# p2gs-001.net
KiCad netlist of a schematic drawn in EAGLE
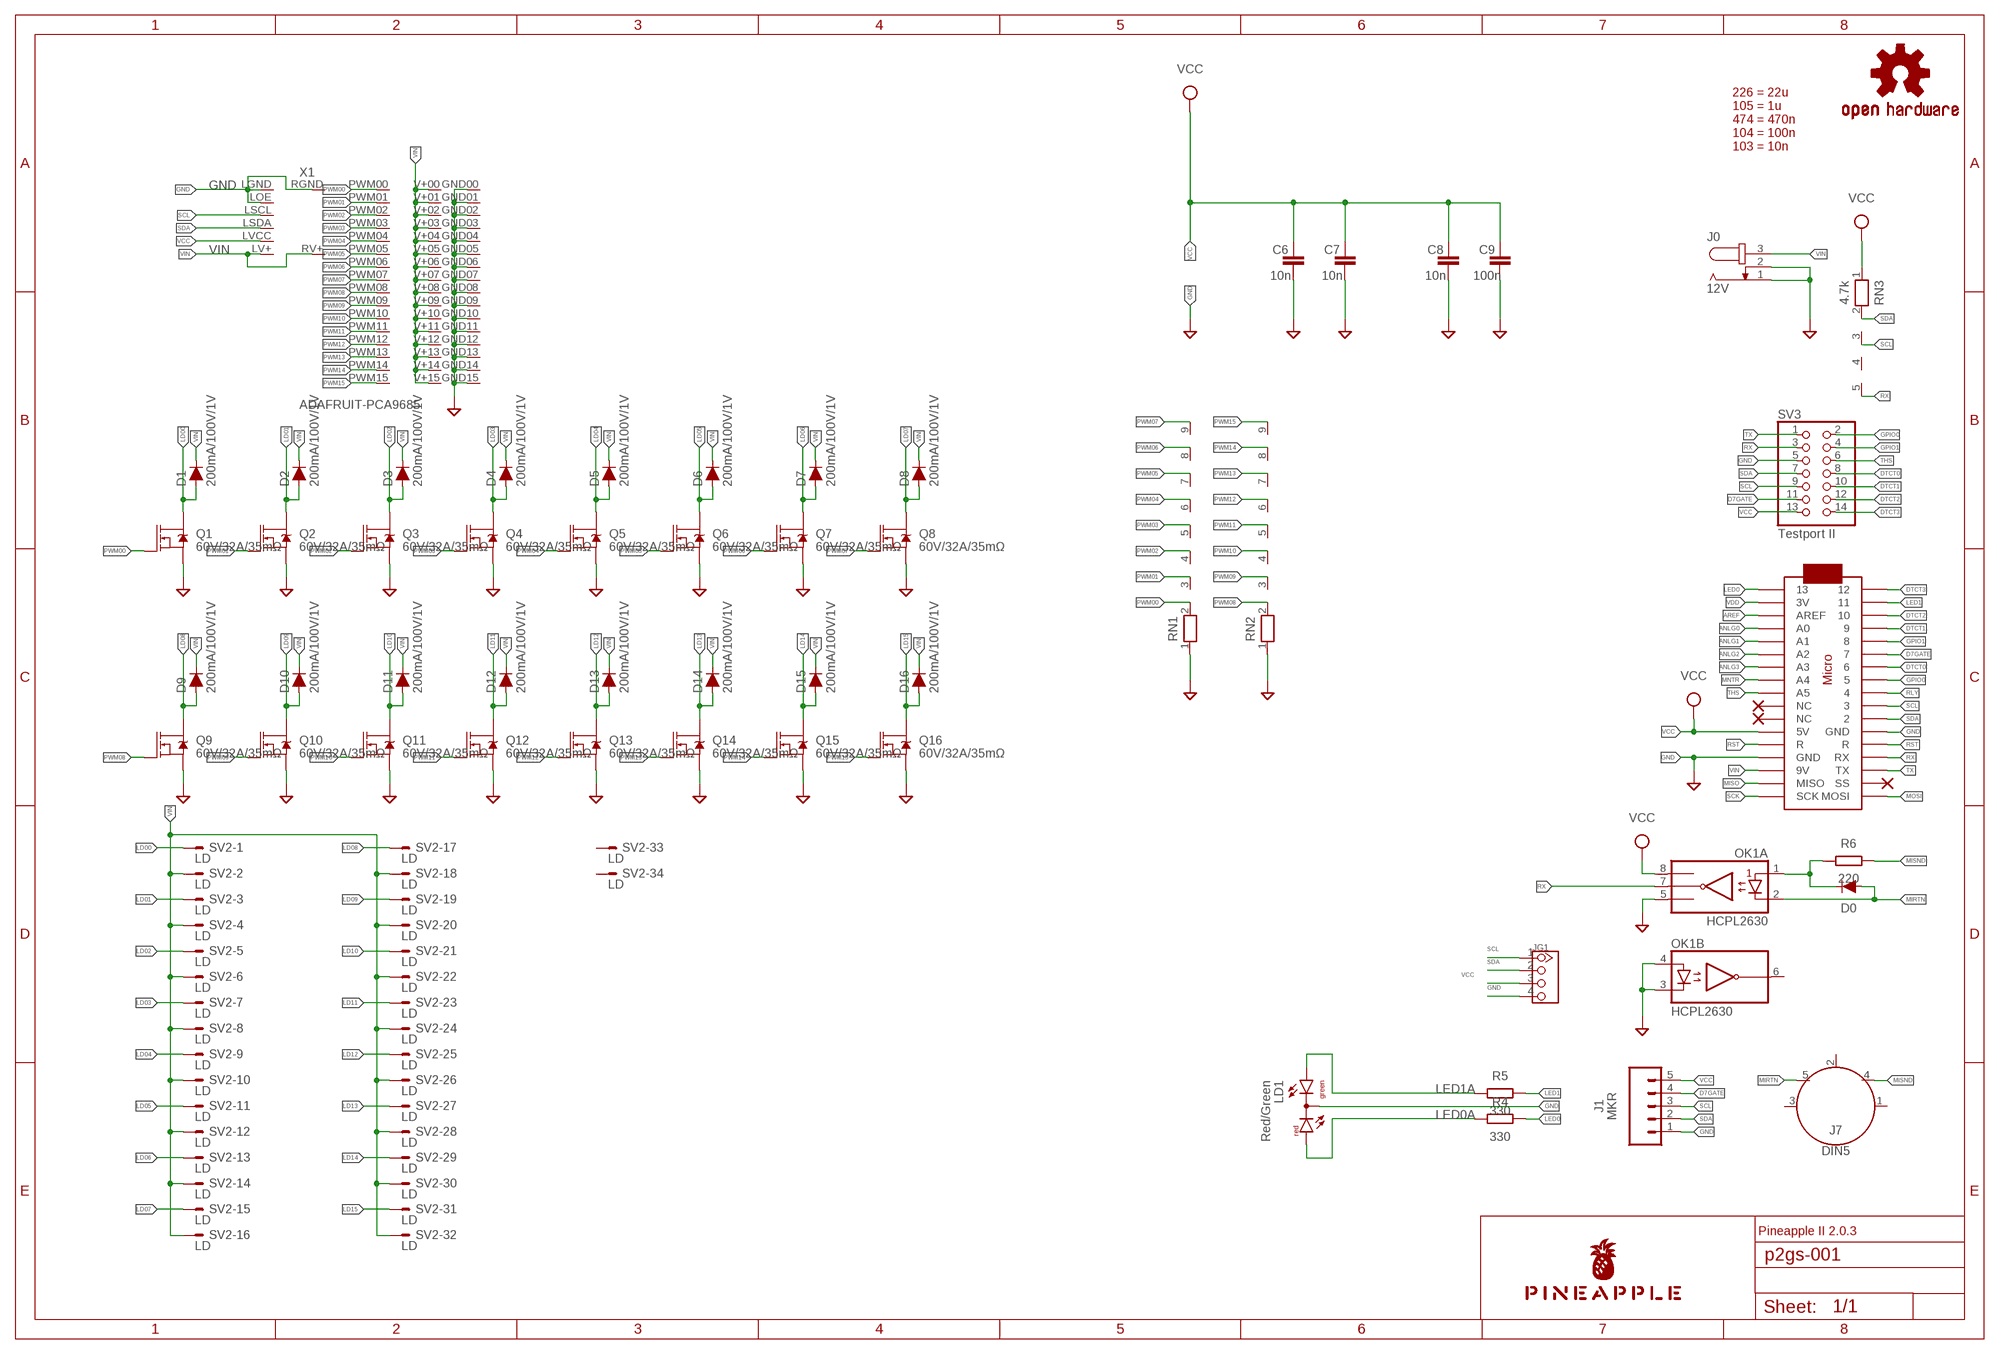
[diagram p0: schematic, sheet 1]

(export (version "E")
  (design (tool "Eeschema 10.0.6"))
  (components
    (comp (ref "C6")
      (value "10n")
      (footprint "eagle-import:C025-024X044")
      (libsource (lib "eagle-import") (part "C-EU025-024X044"))
    )
    (comp (ref "C7")
      (value "10n")
      (footprint "eagle-import:C025-024X044")
      (libsource (lib "eagle-import") (part "C-EU025-024X044"))
    )
    (comp (ref "C8")
      (value "10n")
      (footprint "eagle-import:C025-024X044")
      (libsource (lib "eagle-import") (part "C-EU025-024X044"))
    )
    (comp (ref "C9")
      (value "100n")
      (footprint "eagle-import:C025-024X044")
      (libsource (lib "eagle-import") (part "C-EU025-024X044"))
    )
    (comp (ref "D0")
      (value "DIODE-1N4148")
      (footprint "eagle-import:DIODE-1N4148")
      (libsource (lib "eagle-import") (part "DIODE-1N4148"))
    )
    (comp (ref "D1")
      (value "200mA/100V/1V")
      (footprint "eagle-import:DIODE-1N4148")
      (libsource (lib "eagle-import") (part "DIODE-1N4148"))
    )
    (comp (ref "D2")
      (value "200mA/100V/1V")
      (footprint "eagle-import:DIODE-1N4148")
      (libsource (lib "eagle-import") (part "DIODE-1N4148"))
    )
    (comp (ref "D3")
      (value "200mA/100V/1V")
      (footprint "eagle-import:DIODE-1N4148")
      (libsource (lib "eagle-import") (part "DIODE-1N4148"))
    )
    (comp (ref "D4")
      (value "200mA/100V/1V")
      (footprint "eagle-import:DIODE-1N4148")
      (libsource (lib "eagle-import") (part "DIODE-1N4148"))
    )
    (comp (ref "D5")
      (value "200mA/100V/1V")
      (footprint "eagle-import:DIODE-1N4148")
      (libsource (lib "eagle-import") (part "DIODE-1N4148"))
    )
    (comp (ref "D6")
      (value "200mA/100V/1V")
      (footprint "eagle-import:DIODE-1N4148")
      (libsource (lib "eagle-import") (part "DIODE-1N4148"))
    )
    (comp (ref "D7")
      (value "200mA/100V/1V")
      (footprint "eagle-import:DIODE-1N4148")
      (libsource (lib "eagle-import") (part "DIODE-1N4148"))
    )
    (comp (ref "D8")
      (value "200mA/100V/1V")
      (footprint "eagle-import:DIODE-1N4148")
      (libsource (lib "eagle-import") (part "DIODE-1N4148"))
    )
    (comp (ref "D9")
      (value "200mA/100V/1V")
      (footprint "eagle-import:DIODE-1N4148")
      (libsource (lib "eagle-import") (part "DIODE-1N4148"))
    )
    (comp (ref "D10")
      (value "200mA/100V/1V")
      (footprint "eagle-import:DIODE-1N4148")
      (libsource (lib "eagle-import") (part "DIODE-1N4148"))
    )
    (comp (ref "D11")
      (value "200mA/100V/1V")
      (footprint "eagle-import:DIODE-1N4148")
      (libsource (lib "eagle-import") (part "DIODE-1N4148"))
    )
    (comp (ref "D12")
      (value "200mA/100V/1V")
      (footprint "eagle-import:DIODE-1N4148")
      (libsource (lib "eagle-import") (part "DIODE-1N4148"))
    )
    (comp (ref "D13")
      (value "200mA/100V/1V")
      (footprint "eagle-import:DIODE-1N4148")
      (libsource (lib "eagle-import") (part "DIODE-1N4148"))
    )
    (comp (ref "D14")
      (value "200mA/100V/1V")
      (footprint "eagle-import:DIODE-1N4148")
      (libsource (lib "eagle-import") (part "DIODE-1N4148"))
    )
    (comp (ref "D15")
      (value "200mA/100V/1V")
      (footprint "eagle-import:DIODE-1N4148")
      (libsource (lib "eagle-import") (part "DIODE-1N4148"))
    )
    (comp (ref "D16")
      (value "200mA/100V/1V")
      (footprint "eagle-import:DIODE-1N4148")
      (libsource (lib "eagle-import") (part "DIODE-1N4148"))
    )
    (comp (ref "J0")
      (value "12V")
      (footprint "eagle-import:SPC4077")
      (libsource (lib "eagle-import") (part "JACK-PLUG0"))
    )
    (comp (ref "J1")
      (value "MKR")
      (footprint "eagle-import:JST-5-PTH")
      (libsource (lib "eagle-import") (part "CONN_05JST"))
    )
    (comp (ref "J7")
      (value "DIN5")
      (footprint "eagle-import:DIN5-RA-PTH")
      (libsource (lib "eagle-import") (part "DIN5"))
    )
    (comp (ref "JG1")
      (value "TWIG-4P-2.0'90D'")
      (footprint "eagle-import:4P-2.0-90D")
      (libsource (lib "eagle-import") (part "TWIG-4P-2.0'90D'"))
    )
    (comp (ref "LD1")
      (value "Red/Green")
      (footprint "eagle-import:DUOLED-C-5MM")
      (libsource (lib "eagle-import") (part "DUOLED-RG-C"))
    )
    (comp (ref "LOGO1")
      (value "OSHW-LOGOS-COPPER")
      (footprint "eagle-import:OSHW-LOGO-S_COPPER")
      (libsource (lib "eagle-import") (part "OSHW-LOGOS-COPPER"))
    )
    (comp (ref "MC1")
      (value "ARDUINOMICRO")
      (footprint "eagle-import:ARDUINOMICRO")
      (libsource (lib "eagle-import") (part "ARDUINOMICRO"))
    )
    (comp (ref "OK1")
      (value "HCPL2630")
      (footprint "eagle-import:DIL08")
      (fields (field (name "MF") "AGILENT TECHNOLOGIES") (field (name "MPN") "HCPL-2630-000E"))
      (libsource (lib "eagle-import") (part "HCPL2630"))
    )
    (comp (ref "Q1")
      (value "60V/32A/35mΩ")
      (footprint "eagle-import:TO220V")
      (libsource (lib "eagle-import") (part "MOSFET-NCH-FQP30N06L"))
    )
    (comp (ref "Q2")
      (value "60V/32A/35mΩ")
      (footprint "eagle-import:TO220V")
      (libsource (lib "eagle-import") (part "MOSFET-NCH-FQP30N06L"))
    )
    (comp (ref "Q3")
      (value "60V/32A/35mΩ")
      (footprint "eagle-import:TO220V")
      (libsource (lib "eagle-import") (part "MOSFET-NCH-FQP30N06L"))
    )
    (comp (ref "Q4")
      (value "60V/32A/35mΩ")
      (footprint "eagle-import:TO220V")
      (libsource (lib "eagle-import") (part "MOSFET-NCH-FQP30N06L"))
    )
    (comp (ref "Q5")
      (value "60V/32A/35mΩ")
      (footprint "eagle-import:TO220V")
      (libsource (lib "eagle-import") (part "MOSFET-NCH-FQP30N06L"))
    )
    (comp (ref "Q6")
      (value "60V/32A/35mΩ")
      (footprint "eagle-import:TO220V")
      (libsource (lib "eagle-import") (part "MOSFET-NCH-FQP30N06L"))
    )
    (comp (ref "Q7")
      (value "60V/32A/35mΩ")
      (footprint "eagle-import:TO220V")
      (libsource (lib "eagle-import") (part "MOSFET-NCH-FQP30N06L"))
    )
    (comp (ref "Q8")
      (value "60V/32A/35mΩ")
      (footprint "eagle-import:TO220V")
      (libsource (lib "eagle-import") (part "MOSFET-NCH-FQP30N06L"))
    )
    (comp (ref "Q9")
      (value "60V/32A/35mΩ")
      (footprint "eagle-import:TO220V")
      (libsource (lib "eagle-import") (part "MOSFET-NCH-FQP30N06L"))
    )
    (comp (ref "Q10")
      (value "60V/32A/35mΩ")
      (footprint "eagle-import:TO220V")
      (libsource (lib "eagle-import") (part "MOSFET-NCH-FQP30N06L"))
    )
    (comp (ref "Q11")
      (value "60V/32A/35mΩ")
      (footprint "eagle-import:TO220V")
      (libsource (lib "eagle-import") (part "MOSFET-NCH-FQP30N06L"))
    )
    (comp (ref "Q12")
      (value "60V/32A/35mΩ")
      (footprint "eagle-import:TO220V")
      (libsource (lib "eagle-import") (part "MOSFET-NCH-FQP30N06L"))
    )
    (comp (ref "Q13")
      (value "60V/32A/35mΩ")
      (footprint "eagle-import:TO220V")
      (libsource (lib "eagle-import") (part "MOSFET-NCH-FQP30N06L"))
    )
    (comp (ref "Q14")
      (value "60V/32A/35mΩ")
      (footprint "eagle-import:TO220V")
      (libsource (lib "eagle-import") (part "MOSFET-NCH-FQP30N06L"))
    )
    (comp (ref "Q15")
      (value "60V/32A/35mΩ")
      (footprint "eagle-import:TO220V")
      (libsource (lib "eagle-import") (part "MOSFET-NCH-FQP30N06L"))
    )
    (comp (ref "Q16")
      (value "60V/32A/35mΩ")
      (footprint "eagle-import:TO220V")
      (libsource (lib "eagle-import") (part "MOSFET-NCH-FQP30N06L"))
    )
    (comp (ref "R4")
      (value "330")
      (footprint "eagle-import:0204_5")
      (libsource (lib "eagle-import") (part "R-EU_0204/5"))
    )
    (comp (ref "R5")
      (value "330")
      (footprint "eagle-import:0204_5")
      (libsource (lib "eagle-import") (part "R-EU_0204/5"))
    )
    (comp (ref "R6")
      (value "220")
      (footprint "eagle-import:0204_5")
      (libsource (lib "eagle-import") (part "R-EU_0204/5"))
    )
    (comp (ref "RN1")
      (value "RN08")
      (footprint "eagle-import:RN-9")
      (libsource (lib "eagle-import") (part "RN08"))
    )
    (comp (ref "RN2")
      (value "RN08")
      (footprint "eagle-import:RN-9")
      (libsource (lib "eagle-import") (part "RN08"))
    )
    (comp (ref "RN3")
      (value "4.7k")
      (footprint "eagle-import:RN-5")
      (libsource (lib "eagle-import") (part "RN04"))
    )
    (comp (ref "SV2")
      (value "LD")
      (footprint "eagle-import:ML34L")
      (libsource (lib "eagle-import") (part "ML34LE"))
    )
    (comp (ref "SV3")
      (value "Testport II")
      (footprint "eagle-import:2X07")
      (libsource (lib "eagle-import") (part "PINHD-2X7"))
    )
    (comp (ref "U$1")
      (value "PINEAPPLE450_SILK")
      (footprint "eagle-import:PINEAPPLE450_SILK")
      (libsource (lib "eagle-import") (part "PINEAPPLE450_SILK"))
    )
    (comp (ref "X1")
      (value "ADAFRUIT-PCA9685")
      (footprint "eagle-import:ADAFRUIT-PCA9685-FOOTPRINT")
      (libsource (lib "eagle-import") (part "ADAFRUIT-PCA9685"))
    )
  )
  (nets
    (net (code "1") (name "/LED0A") (class "Default")
      (node (ref "LD1") (pin "AR") (pinfunction "AR_AR") (pintype "passive"))
      (node (ref "R4") (pin "1") (pinfunction "1_1") (pintype "passive"))
    )
    (net (code "2") (name "/LED1A") (class "Default")
      (node (ref "LD1") (pin "AX") (pinfunction "AG_AX") (pintype "passive"))
      (node (ref "R5") (pin "1") (pinfunction "1_1") (pintype "passive"))
    )
    (net (code "3") (name "ANLG0") (class "Default")
      (node (ref "MC1") (pin "P$31") (pinfunction "A0_P$31") (pintype "bidirectional"))
    )
    (net (code "4") (name "ANLG1") (class "Default")
      (node (ref "MC1") (pin "P$30") (pinfunction "A1_P$30") (pintype "bidirectional"))
    )
    (net (code "5") (name "ANLG2") (class "Default")
      (node (ref "MC1") (pin "P$29") (pinfunction "A2_P$29") (pintype "bidirectional"))
    )
    (net (code "6") (name "ANLG3") (class "Default")
      (node (ref "MC1") (pin "P$28") (pinfunction "A3_P$28") (pintype "bidirectional"))
    )
    (net (code "7") (name "AREF") (class "Default")
      (node (ref "MC1") (pin "P$32") (pinfunction "AREF_P$32") (pintype "bidirectional"))
    )
    (net (code "8") (name "D7GATE") (class "Default")
      (node (ref "J1") (pin "4") (pinfunction "4_4") (pintype "passive"))
      (node (ref "MC1") (pin "P$6") (pinfunction "7_P$6") (pintype "bidirectional"))
      (node (ref "SV3") (pin "11") (pinfunction "11_11") (pintype "passive"))
    )
    (net (code "9") (name "DTCT0") (class "Default")
      (node (ref "MC1") (pin "P$7") (pinfunction "6_P$7") (pintype "bidirectional"))
      (node (ref "SV3") (pin "8") (pinfunction "8_8") (pintype "passive"))
    )
    (net (code "10") (name "DTCT1") (class "Default")
      (node (ref "MC1") (pin "P$4") (pinfunction "9_P$4") (pintype "bidirectional"))
      (node (ref "SV3") (pin "10") (pinfunction "10_10") (pintype "passive"))
    )
    (net (code "11") (name "DTCT2") (class "Default")
      (node (ref "MC1") (pin "P$3") (pinfunction "10_P$3") (pintype "bidirectional"))
      (node (ref "SV3") (pin "12") (pinfunction "12_12") (pintype "passive"))
    )
    (net (code "12") (name "DTCT3") (class "Default")
      (node (ref "MC1") (pin "P$1") (pinfunction "12_P$1") (pintype "bidirectional"))
      (node (ref "SV3") (pin "14") (pinfunction "14_14") (pintype "passive"))
    )
    (net (code "13") (name "GND") (class "Default")
      (node (ref "C6") (pin "2") (pinfunction "2_2") (pintype "passive"))
      (node (ref "C7") (pin "2") (pinfunction "2_2") (pintype "passive"))
      (node (ref "C8") (pin "2") (pinfunction "2_2") (pintype "passive"))
      (node (ref "C9") (pin "2") (pinfunction "2_2") (pintype "passive"))
      (node (ref "J0") (pin "1") (pinfunction "1_1") (pintype "passive"))
      (node (ref "J0") (pin "2") (pinfunction "2_2") (pintype "passive"))
      (node (ref "J1") (pin "1") (pinfunction "1_1") (pintype "passive"))
      (node (ref "JG1") (pin "4") (pinfunction "4_4") (pintype "bidirectional"))
      (node (ref "LD1") (pin "C") (pinfunction "C_C") (pintype "passive"))
      (node (ref "MC1") (pin "P$12") (pinfunction "GND_P$12") (pintype "bidirectional"))
      (node (ref "MC1") (pin "P$21") (pinfunction "GND_P$21") (pintype "bidirectional"))
      (node (ref "OK1") (pin "3") (pinfunction "C2_3") (pintype "passive"))
      (node (ref "OK1") (pin "4") (pinfunction "A2_4") (pintype "passive"))
      (node (ref "OK1") (pin "5") (pinfunction "GND_5") (pintype "passive"))
      (node (ref "Q1") (pin "3") (pinfunction "S_3") (pintype "bidirectional"))
      (node (ref "Q10") (pin "3") (pinfunction "S_3") (pintype "bidirectional"))
      (node (ref "Q11") (pin "3") (pinfunction "S_3") (pintype "bidirectional"))
      (node (ref "Q12") (pin "3") (pinfunction "S_3") (pintype "bidirectional"))
      (node (ref "Q13") (pin "3") (pinfunction "S_3") (pintype "bidirectional"))
      (node (ref "Q14") (pin "3") (pinfunction "S_3") (pintype "bidirectional"))
      (node (ref "Q15") (pin "3") (pinfunction "S_3") (pintype "bidirectional"))
      (node (ref "Q16") (pin "3") (pinfunction "S_3") (pintype "bidirectional"))
      (node (ref "Q2") (pin "3") (pinfunction "S_3") (pintype "bidirectional"))
      (node (ref "Q3") (pin "3") (pinfunction "S_3") (pintype "bidirectional"))
      (node (ref "Q4") (pin "3") (pinfunction "S_3") (pintype "bidirectional"))
      (node (ref "Q5") (pin "3") (pinfunction "S_3") (pintype "bidirectional"))
      (node (ref "Q6") (pin "3") (pinfunction "S_3") (pintype "bidirectional"))
      (node (ref "Q7") (pin "3") (pinfunction "S_3") (pintype "bidirectional"))
      (node (ref "Q8") (pin "3") (pinfunction "S_3") (pintype "bidirectional"))
      (node (ref "Q9") (pin "3") (pinfunction "S_3") (pintype "bidirectional"))
      (node (ref "RN1") (pin "1") (pinfunction "1_1") (pintype "passive"))
      (node (ref "RN2") (pin "1") (pinfunction "1_1") (pintype "passive"))
      (node (ref "SV3") (pin "5") (pinfunction "5_5") (pintype "passive"))
      (node (ref "X1") (pin "GND00") (pinfunction "45_GND00") (pintype "passive"))
      (node (ref "X1") (pin "GND01") (pinfunction "46_GND01") (pintype "passive"))
      (node (ref "X1") (pin "GND02") (pinfunction "47_GND02") (pintype "passive"))
      (node (ref "X1") (pin "GND03") (pinfunction "48_GND03") (pintype "passive"))
      (node (ref "X1") (pin "GND04") (pinfunction "49_GND04") (pintype "passive"))
      (node (ref "X1") (pin "GND05") (pinfunction "50_GND05") (pintype "passive"))
      (node (ref "X1") (pin "GND06") (pinfunction "51_GND06") (pintype "passive"))
      (node (ref "X1") (pin "GND07") (pinfunction "52_GND07") (pintype "passive"))
      (node (ref "X1") (pin "GND08") (pinfunction "53_GND08") (pintype "passive"))
      (node (ref "X1") (pin "GND09") (pinfunction "54_GND09") (pintype "passive"))
      (node (ref "X1") (pin "GND10") (pinfunction "55_GND10") (pintype "passive"))
      (node (ref "X1") (pin "GND11") (pinfunction "56_GND11") (pintype "passive"))
      (node (ref "X1") (pin "GND12") (pinfunction "57_GND12") (pintype "passive"))
      (node (ref "X1") (pin "GND13") (pinfunction "58_GND13") (pintype "passive"))
      (node (ref "X1") (pin "GND14") (pinfunction "59_GND14") (pintype "passive"))
      (node (ref "X1") (pin "GND15") (pinfunction "60_GND15") (pintype "passive"))
      (node (ref "X1") (pin "LGND") (pinfunction "1_LGND") (pintype "passive"))
      (node (ref "X1") (pin "LOE") (pinfunction "2_LOE") (pintype "passive"))
      (node (ref "X1") (pin "RGND") (pinfunction "7_RGND") (pintype "passive"))
    )
    (net (code "14") (name "GPIO0") (class "Default")
      (node (ref "MC1") (pin "P$8") (pinfunction "5_P$8") (pintype "bidirectional"))
      (node (ref "SV3") (pin "2") (pinfunction "2_2") (pintype "passive"))
    )
    (net (code "15") (name "GPIO1") (class "Default")
      (node (ref "MC1") (pin "P$5") (pinfunction "8_P$5") (pintype "bidirectional"))
      (node (ref "SV3") (pin "4") (pinfunction "4_4") (pintype "passive"))
    )
    (net (code "16") (name "LD00") (class "Default")
      (node (ref "D1") (pin "A") (pinfunction "A_A") (pintype "passive"))
      (node (ref "Q1") (pin "2") (pinfunction "D_2") (pintype "bidirectional"))
      (node (ref "SV2") (pin "1") (pinfunction "S_1") (pintype "passive"))
    )
    (net (code "17") (name "LD01") (class "Default")
      (node (ref "D2") (pin "A") (pinfunction "A_A") (pintype "passive"))
      (node (ref "Q2") (pin "2") (pinfunction "D_2") (pintype "bidirectional"))
      (node (ref "SV2") (pin "3") (pinfunction "S_3") (pintype "passive"))
    )
    (net (code "18") (name "LD02") (class "Default")
      (node (ref "D3") (pin "A") (pinfunction "A_A") (pintype "passive"))
      (node (ref "Q3") (pin "2") (pinfunction "D_2") (pintype "bidirectional"))
      (node (ref "SV2") (pin "5") (pinfunction "S_5") (pintype "passive"))
    )
    (net (code "19") (name "LD03") (class "Default")
      (node (ref "D4") (pin "A") (pinfunction "A_A") (pintype "passive"))
      (node (ref "Q4") (pin "2") (pinfunction "D_2") (pintype "bidirectional"))
      (node (ref "SV2") (pin "7") (pinfunction "S_7") (pintype "passive"))
    )
    (net (code "20") (name "LD04") (class "Default")
      (node (ref "D5") (pin "A") (pinfunction "A_A") (pintype "passive"))
      (node (ref "Q5") (pin "2") (pinfunction "D_2") (pintype "bidirectional"))
      (node (ref "SV2") (pin "9") (pinfunction "S_9") (pintype "passive"))
    )
    (net (code "21") (name "LD05") (class "Default")
      (node (ref "D6") (pin "A") (pinfunction "A_A") (pintype "passive"))
      (node (ref "Q6") (pin "2") (pinfunction "D_2") (pintype "bidirectional"))
      (node (ref "SV2") (pin "11") (pinfunction "S_11") (pintype "passive"))
    )
    (net (code "22") (name "LD06") (class "Default")
      (node (ref "D7") (pin "A") (pinfunction "A_A") (pintype "passive"))
      (node (ref "Q7") (pin "2") (pinfunction "D_2") (pintype "bidirectional"))
      (node (ref "SV2") (pin "13") (pinfunction "S_13") (pintype "passive"))
    )
    (net (code "23") (name "LD07") (class "Default")
      (node (ref "D8") (pin "A") (pinfunction "A_A") (pintype "passive"))
      (node (ref "Q8") (pin "2") (pinfunction "D_2") (pintype "bidirectional"))
      (node (ref "SV2") (pin "15") (pinfunction "S_15") (pintype "passive"))
    )
    (net (code "24") (name "LD08") (class "Default")
      (node (ref "D9") (pin "A") (pinfunction "A_A") (pintype "passive"))
      (node (ref "Q9") (pin "2") (pinfunction "D_2") (pintype "bidirectional"))
      (node (ref "SV2") (pin "17") (pinfunction "S_17") (pintype "passive"))
    )
    (net (code "25") (name "LD09") (class "Default")
      (node (ref "D10") (pin "A") (pinfunction "A_A") (pintype "passive"))
      (node (ref "Q10") (pin "2") (pinfunction "D_2") (pintype "bidirectional"))
      (node (ref "SV2") (pin "19") (pinfunction "S_19") (pintype "passive"))
    )
    (net (code "26") (name "LD10") (class "Default")
      (node (ref "D11") (pin "A") (pinfunction "A_A") (pintype "passive"))
      (node (ref "Q11") (pin "2") (pinfunction "D_2") (pintype "bidirectional"))
      (node (ref "SV2") (pin "21") (pinfunction "S_21") (pintype "passive"))
    )
    (net (code "27") (name "LD11") (class "Default")
      (node (ref "D12") (pin "A") (pinfunction "A_A") (pintype "passive"))
      (node (ref "Q12") (pin "2") (pinfunction "D_2") (pintype "bidirectional"))
      (node (ref "SV2") (pin "23") (pinfunction "S_23") (pintype "passive"))
    )
    (net (code "28") (name "LD12") (class "Default")
      (node (ref "D13") (pin "A") (pinfunction "A_A") (pintype "passive"))
      (node (ref "Q13") (pin "2") (pinfunction "D_2") (pintype "bidirectional"))
      (node (ref "SV2") (pin "25") (pinfunction "S_25") (pintype "passive"))
    )
    (net (code "29") (name "LD13") (class "Default")
      (node (ref "D14") (pin "A") (pinfunction "A_A") (pintype "passive"))
      (node (ref "Q14") (pin "2") (pinfunction "D_2") (pintype "bidirectional"))
      (node (ref "SV2") (pin "27") (pinfunction "S_27") (pintype "passive"))
    )
    (net (code "30") (name "LD14") (class "Default")
      (node (ref "D15") (pin "A") (pinfunction "A_A") (pintype "passive"))
      (node (ref "Q15") (pin "2") (pinfunction "D_2") (pintype "bidirectional"))
      (node (ref "SV2") (pin "29") (pinfunction "S_29") (pintype "passive"))
    )
    (net (code "31") (name "LD15") (class "Default")
      (node (ref "D16") (pin "A") (pinfunction "A_A") (pintype "passive"))
      (node (ref "Q16") (pin "2") (pinfunction "D_2") (pintype "bidirectional"))
      (node (ref "SV2") (pin "31") (pinfunction "S_31") (pintype "passive"))
    )
    (net (code "32") (name "LED0") (class "Default")
      (node (ref "MC1") (pin "P$34") (pinfunction "13_P$34") (pintype "bidirectional"))
      (node (ref "R4") (pin "2") (pinfunction "2_2") (pintype "passive"))
    )
    (net (code "33") (name "LED1") (class "Default")
      (node (ref "MC1") (pin "P$2") (pinfunction "11_P$2") (pintype "bidirectional"))
      (node (ref "R5") (pin "2") (pinfunction "2_2") (pintype "passive"))
    )
    (net (code "34") (name "MIRTN") (class "Default")
      (node (ref "D0") (pin "A") (pinfunction "A_A") (pintype "passive"))
      (node (ref "J7") (pin "5") (pinfunction "5_5") (pintype "bidirectional"))
      (node (ref "OK1") (pin "2") (pinfunction "C1_2") (pintype "passive"))
    )
    (net (code "35") (name "MISND") (class "Default")
      (node (ref "J7") (pin "4") (pinfunction "4_4") (pintype "bidirectional"))
      (node (ref "R6") (pin "2") (pinfunction "2_2") (pintype "passive"))
    )
    (net (code "36") (name "MISO") (class "Default")
      (node (ref "MC1") (pin "P$19") (pinfunction "MISO_P$19") (pintype "bidirectional"))
    )
    (net (code "37") (name "MNTR") (class "Default")
      (node (ref "MC1") (pin "P$27") (pinfunction "A4_P$27") (pintype "bidirectional"))
    )
    (net (code "38") (name "MOSI") (class "Default")
      (node (ref "MC1") (pin "P$17") (pinfunction "MOSI_P$17") (pintype "bidirectional"))
    )
    (net (code "39") (name "Net-(OK1A-A1)") (class "Default")
      (node (ref "D0") (pin "C") (pinfunction "C_C") (pintype "passive"))
      (node (ref "OK1") (pin "1") (pinfunction "A1_1") (pintype "passive"))
      (node (ref "R6") (pin "1") (pinfunction "1_1") (pintype "passive"))
    )
    (net (code "40") (name "PWM00") (class "Default")
      (node (ref "Q1") (pin "1") (pinfunction "G_1") (pintype "bidirectional"))
      (node (ref "RN1") (pin "2") (pinfunction "2_2") (pintype "passive"))
      (node (ref "X1") (pin "PWM00") (pinfunction "13_PWM00") (pintype "passive"))
    )
    (net (code "41") (name "PWM01") (class "Default")
      (node (ref "Q2") (pin "1") (pinfunction "G_1") (pintype "bidirectional"))
      (node (ref "RN1") (pin "3") (pinfunction "3_3") (pintype "passive"))
      (node (ref "X1") (pin "PWM01") (pinfunction "14_PWM01") (pintype "passive"))
    )
    (net (code "42") (name "PWM02") (class "Default")
      (node (ref "Q3") (pin "1") (pinfunction "G_1") (pintype "bidirectional"))
      (node (ref "RN1") (pin "4") (pinfunction "4_4") (pintype "passive"))
      (node (ref "X1") (pin "PWM02") (pinfunction "15_PWM02") (pintype "passive"))
    )
    (net (code "43") (name "PWM03") (class "Default")
      (node (ref "Q4") (pin "1") (pinfunction "G_1") (pintype "bidirectional"))
      (node (ref "RN1") (pin "5") (pinfunction "5_5") (pintype "passive"))
      (node (ref "X1") (pin "PWM03") (pinfunction "16_PWM03") (pintype "passive"))
    )
    (net (code "44") (name "PWM04") (class "Default")
      (node (ref "Q5") (pin "1") (pinfunction "G_1") (pintype "bidirectional"))
      (node (ref "RN1") (pin "6") (pinfunction "6_6") (pintype "passive"))
      (node (ref "X1") (pin "PWM04") (pinfunction "17_PWM04") (pintype "passive"))
    )
    (net (code "45") (name "PWM05") (class "Default")
      (node (ref "Q6") (pin "1") (pinfunction "G_1") (pintype "bidirectional"))
      (node (ref "RN1") (pin "7") (pinfunction "7_7") (pintype "passive"))
      (node (ref "X1") (pin "PWM05") (pinfunction "18_PWM05") (pintype "passive"))
    )
    (net (code "46") (name "PWM06") (class "Default")
      (node (ref "Q7") (pin "1") (pinfunction "G_1") (pintype "bidirectional"))
      (node (ref "RN1") (pin "8") (pinfunction "8_8") (pintype "passive"))
      (node (ref "X1") (pin "PWM06") (pinfunction "19_PWM06") (pintype "passive"))
    )
    (net (code "47") (name "PWM07") (class "Default")
      (node (ref "Q8") (pin "1") (pinfunction "G_1") (pintype "bidirectional"))
      (node (ref "RN1") (pin "9") (pinfunction "9_9") (pintype "passive"))
      (node (ref "X1") (pin "PWM07") (pinfunction "20_PWM07") (pintype "passive"))
    )
    (net (code "48") (name "PWM08") (class "Default")
      (node (ref "Q9") (pin "1") (pinfunction "G_1") (pintype "bidirectional"))
      (node (ref "RN2") (pin "2") (pinfunction "2_2") (pintype "passive"))
      (node (ref "X1") (pin "PWM08") (pinfunction "21_PWM08") (pintype "passive"))
    )
    (net (code "49") (name "PWM09") (class "Default")
      (node (ref "Q10") (pin "1") (pinfunction "G_1") (pintype "bidirectional"))
      (node (ref "RN2") (pin "3") (pinfunction "3_3") (pintype "passive"))
      (node (ref "X1") (pin "PWM09") (pinfunction "22_PWM09") (pintype "passive"))
    )
    (net (code "50") (name "PWM10") (class "Default")
      (node (ref "Q11") (pin "1") (pinfunction "G_1") (pintype "bidirectional"))
      (node (ref "RN2") (pin "4") (pinfunction "4_4") (pintype "passive"))
      (node (ref "X1") (pin "PWM10") (pinfunction "23_PWM10") (pintype "passive"))
    )
    (net (code "51") (name "PWM11") (class "Default")
      (node (ref "Q12") (pin "1") (pinfunction "G_1") (pintype "bidirectional"))
      (node (ref "RN2") (pin "5") (pinfunction "5_5") (pintype "passive"))
      (node (ref "X1") (pin "PWM11") (pinfunction "24_PWM11") (pintype "passive"))
    )
    (net (code "52") (name "PWM12") (class "Default")
      (node (ref "Q13") (pin "1") (pinfunction "G_1") (pintype "bidirectional"))
      (node (ref "RN2") (pin "6") (pinfunction "6_6") (pintype "passive"))
      (node (ref "X1") (pin "PWM12") (pinfunction "25_PWM12") (pintype "passive"))
    )
    (net (code "53") (name "PWM13") (class "Default")
      (node (ref "Q14") (pin "1") (pinfunction "G_1") (pintype "bidirectional"))
      (node (ref "RN2") (pin "7") (pinfunction "7_7") (pintype "passive"))
      (node (ref "X1") (pin "PWM13") (pinfunction "26_PWM13") (pintype "passive"))
    )
    (net (code "54") (name "PWM14") (class "Default")
      (node (ref "Q15") (pin "1") (pinfunction "G_1") (pintype "bidirectional"))
      (node (ref "RN2") (pin "8") (pinfunction "8_8") (pintype "passive"))
      (node (ref "X1") (pin "PWM14") (pinfunction "27_PWM14") (pintype "passive"))
    )
    (net (code "55") (name "PWM15") (class "Default")
      (node (ref "Q16") (pin "1") (pinfunction "G_1") (pintype "bidirectional"))
      (node (ref "RN2") (pin "9") (pinfunction "9_9") (pintype "passive"))
      (node (ref "X1") (pin "PWM15") (pinfunction "28_PWM15") (pintype "passive"))
    )
    (net (code "56") (name "RLY") (class "Default")
      (node (ref "MC1") (pin "P$9") (pinfunction "4_P$9") (pintype "bidirectional"))
    )
    (net (code "57") (name "RST") (class "Default")
      (node (ref "MC1") (pin "P$13") (pinfunction "R_P$13") (pintype "bidirectional"))
      (node (ref "MC1") (pin "P$22") (pinfunction "R_P$22") (pintype "bidirectional"))
    )
    (net (code "58") (name "RX") (class "Default")
      (node (ref "MC1") (pin "P$14") (pinfunction "RX_P$14") (pintype "bidirectional"))
      (node (ref "OK1") (pin "7") (pinfunction "VO1_7") (pintype "passive"))
      (node (ref "RN3") (pin "5") (pinfunction "5_5") (pintype "passive"))
      (node (ref "SV3") (pin "3") (pinfunction "3_3") (pintype "passive"))
    )
    (net (code "59") (name "SCK") (class "Default")
      (node (ref "MC1") (pin "P$18") (pinfunction "SCK_P$18") (pintype "bidirectional"))
    )
    (net (code "60") (name "SCL") (class "Default")
      (node (ref "J1") (pin "3") (pinfunction "3_3") (pintype "passive"))
      (node (ref "JG1") (pin "1") (pinfunction "1_1") (pintype "bidirectional"))
      (node (ref "MC1") (pin "P$10") (pinfunction "3_P$10") (pintype "bidirectional"))
      (node (ref "RN3") (pin "3") (pinfunction "3_3") (pintype "passive"))
      (node (ref "SV3") (pin "9") (pinfunction "9_9") (pintype "passive"))
      (node (ref "X1") (pin "LSCL") (pinfunction "3_LSCL") (pintype "passive"))
    )
    (net (code "61") (name "SDA") (class "Default")
      (node (ref "J1") (pin "2") (pinfunction "2_2") (pintype "passive"))
      (node (ref "JG1") (pin "2") (pinfunction "2_2") (pintype "bidirectional"))
      (node (ref "MC1") (pin "P$11") (pinfunction "2_P$11") (pintype "bidirectional"))
      (node (ref "RN3") (pin "2") (pinfunction "2_2") (pintype "passive"))
      (node (ref "SV3") (pin "7") (pinfunction "7_7") (pintype "passive"))
      (node (ref "X1") (pin "LSDA") (pinfunction "4_LSDA") (pintype "passive"))
    )
    (net (code "62") (name "THS") (class "Default")
      (node (ref "MC1") (pin "P$26") (pinfunction "A5_P$26") (pintype "bidirectional"))
      (node (ref "SV3") (pin "6") (pinfunction "6_6") (pintype "passive"))
    )
    (net (code "63") (name "TX") (class "Default")
      (node (ref "MC1") (pin "P$15") (pinfunction "TX_P$15") (pintype "bidirectional"))
      (node (ref "SV3") (pin "1") (pinfunction "1_1") (pintype "passive"))
    )
    (net (code "64") (name "VCC") (class "Default")
      (node (ref "C6") (pin "1") (pinfunction "1_1") (pintype "passive"))
      (node (ref "C7") (pin "1") (pinfunction "1_1") (pintype "passive"))
      (node (ref "C8") (pin "1") (pinfunction "1_1") (pintype "passive"))
      (node (ref "C9") (pin "1") (pinfunction "1_1") (pintype "passive"))
      (node (ref "J1") (pin "5") (pinfunction "5_5") (pintype "passive"))
      (node (ref "JG1") (pin "3") (pinfunction "3_3") (pintype "bidirectional"))
      (node (ref "MC1") (pin "P$23") (pinfunction "5V_P$23") (pintype "bidirectional"))
      (node (ref "OK1") (pin "8") (pinfunction "VCC_8") (pintype "passive"))
      (node (ref "RN3") (pin "1") (pinfunction "1_1") (pintype "passive"))
      (node (ref "SV3") (pin "13") (pinfunction "13_13") (pintype "passive"))
      (node (ref "X1") (pin "LVCC") (pinfunction "5_LVCC") (pintype "passive"))
    )
    (net (code "65") (name "VDD") (class "Default")
      (node (ref "MC1") (pin "P$33") (pinfunction "3V_P$33") (pintype "bidirectional"))
    )
    (net (code "66") (name "VIN") (class "Default")
      (node (ref "D1") (pin "C") (pinfunction "C_C") (pintype "passive"))
      (node (ref "D10") (pin "C") (pinfunction "C_C") (pintype "passive"))
      (node (ref "D11") (pin "C") (pinfunction "C_C") (pintype "passive"))
      (node (ref "D12") (pin "C") (pinfunction "C_C") (pintype "passive"))
      (node (ref "D13") (pin "C") (pinfunction "C_C") (pintype "passive"))
      (node (ref "D14") (pin "C") (pinfunction "C_C") (pintype "passive"))
      (node (ref "D15") (pin "C") (pinfunction "C_C") (pintype "passive"))
      (node (ref "D16") (pin "C") (pinfunction "C_C") (pintype "passive"))
      (node (ref "D2") (pin "C") (pinfunction "C_C") (pintype "passive"))
      (node (ref "D3") (pin "C") (pinfunction "C_C") (pintype "passive"))
      (node (ref "D4") (pin "C") (pinfunction "C_C") (pintype "passive"))
      (node (ref "D5") (pin "C") (pinfunction "C_C") (pintype "passive"))
      (node (ref "D6") (pin "C") (pinfunction "C_C") (pintype "passive"))
      (node (ref "D7") (pin "C") (pinfunction "C_C") (pintype "passive"))
      (node (ref "D8") (pin "C") (pinfunction "C_C") (pintype "passive"))
      (node (ref "D9") (pin "C") (pinfunction "C_C") (pintype "passive"))
      (node (ref "J0") (pin "3") (pinfunction "3_3") (pintype "passive"))
      (node (ref "MC1") (pin "P$20") (pinfunction "9V_P$20") (pintype "bidirectional"))
      (node (ref "SV2") (pin "10") (pinfunction "S_10") (pintype "passive"))
      (node (ref "SV2") (pin "12") (pinfunction "S_12") (pintype "passive"))
      (node (ref "SV2") (pin "14") (pinfunction "S_14") (pintype "passive"))
      (node (ref "SV2") (pin "16") (pinfunction "S_16") (pintype "passive"))
      (node (ref "SV2") (pin "18") (pinfunction "S_18") (pintype "passive"))
      (node (ref "SV2") (pin "2") (pinfunction "S_2") (pintype "passive"))
      (node (ref "SV2") (pin "20") (pinfunction "S_20") (pintype "passive"))
      (node (ref "SV2") (pin "22") (pinfunction "S_22") (pintype "passive"))
      (node (ref "SV2") (pin "24") (pinfunction "S_24") (pintype "passive"))
      (node (ref "SV2") (pin "26") (pinfunction "S_26") (pintype "passive"))
      (node (ref "SV2") (pin "28") (pinfunction "S_28") (pintype "passive"))
      (node (ref "SV2") (pin "30") (pinfunction "S_30") (pintype "passive"))
      (node (ref "SV2") (pin "32") (pinfunction "S_32") (pintype "passive"))
      (node (ref "SV2") (pin "4") (pinfunction "S_4") (pintype "passive"))
      (node (ref "SV2") (pin "6") (pinfunction "S_6") (pintype "passive"))
      (node (ref "SV2") (pin "8") (pinfunction "S_8") (pintype "passive"))
      (node (ref "X1") (pin "LV+") (pinfunction "6_LV+") (pintype "passive"))
      (node (ref "X1") (pin "RV+") (pinfunction "12_RV+") (pintype "passive"))
      (node (ref "X1") (pin "V+00") (pinfunction "29_V+00") (pintype "passive"))
      (node (ref "X1") (pin "V+01") (pinfunction "30_V+01") (pintype "passive"))
      (node (ref "X1") (pin "V+02") (pinfunction "31_V+02") (pintype "passive"))
      (node (ref "X1") (pin "V+03") (pinfunction "32_V+03") (pintype "passive"))
      (node (ref "X1") (pin "V+04") (pinfunction "33_V+04") (pintype "passive"))
      (node (ref "X1") (pin "V+05") (pinfunction "34_V+05") (pintype "passive"))
      (node (ref "X1") (pin "V+06") (pinfunction "35_V+06") (pintype "passive"))
      (node (ref "X1") (pin "V+07") (pinfunction "36_V+07") (pintype "passive"))
      (node (ref "X1") (pin "V+08") (pinfunction "37_V+08") (pintype "passive"))
      (node (ref "X1") (pin "V+09") (pinfunction "38_V+09") (pintype "passive"))
      (node (ref "X1") (pin "V+10") (pinfunction "39_V+10") (pintype "passive"))
      (node (ref "X1") (pin "V+11") (pinfunction "40_V+11") (pintype "passive"))
      (node (ref "X1") (pin "V+12") (pinfunction "41_V+12") (pintype "passive"))
      (node (ref "X1") (pin "V+13") (pinfunction "42_V+13") (pintype "passive"))
      (node (ref "X1") (pin "V+14") (pinfunction "43_V+14") (pintype "passive"))
      (node (ref "X1") (pin "V+15") (pinfunction "44_V+15") (pintype "passive"))
    )
    (net (code "67") (name "unconnected-(J7-Pad1)") (class "Default")
      (node (ref "J7") (pin "1") (pinfunction "1_1") (pintype "bidirectional"))
    )
    (net (code "68") (name "unconnected-(J7-Pad2)") (class "Default")
      (node (ref "J7") (pin "2") (pinfunction "2_2") (pintype "bidirectional"))
    )
    (net (code "69") (name "unconnected-(J7-Pad3)") (class "Default")
      (node (ref "J7") (pin "3") (pinfunction "3_3") (pintype "bidirectional"))
    )
    (net (code "70") (name "unconnected-(MC1-NC-PadP$24)") (class "Default")
      (node (ref "MC1") (pin "P$24") (pinfunction "NC_P$24") (pintype "bidirectional"))
    )
    (net (code "71") (name "unconnected-(MC1-NC-PadP$25)") (class "Default")
      (node (ref "MC1") (pin "P$25") (pinfunction "NC_P$25") (pintype "bidirectional"))
    )
    (net (code "72") (name "unconnected-(MC1-SS-PadP$16)") (class "Default")
      (node (ref "MC1") (pin "P$16") (pinfunction "SS_P$16") (pintype "bidirectional"))
    )
    (net (code "73") (name "unconnected-(OK1B-VO2-Pad6)") (class "Default")
      (node (ref "OK1") (pin "6") (pinfunction "VO2_6") (pintype "passive"))
    )
    (net (code "74") (name "unconnected-(RN3-Pad4)") (class "Default")
      (node (ref "RN3") (pin "4") (pinfunction "4_4") (pintype "passive"))
    )
    (net (code "75") (name "unconnected-(SV2AA-S-Pad33)") (class "Default")
      (node (ref "SV2") (pin "33") (pinfunction "S_33") (pintype "passive"))
    )
    (net (code "76") (name "unconnected-(SV2AB-S-Pad34)") (class "Default")
      (node (ref "SV2") (pin "34") (pinfunction "S_34") (pintype "passive"))
    )
  )
)
